# TeensyParser.net
KiCad netlist of a schematic drawn in EAGLE
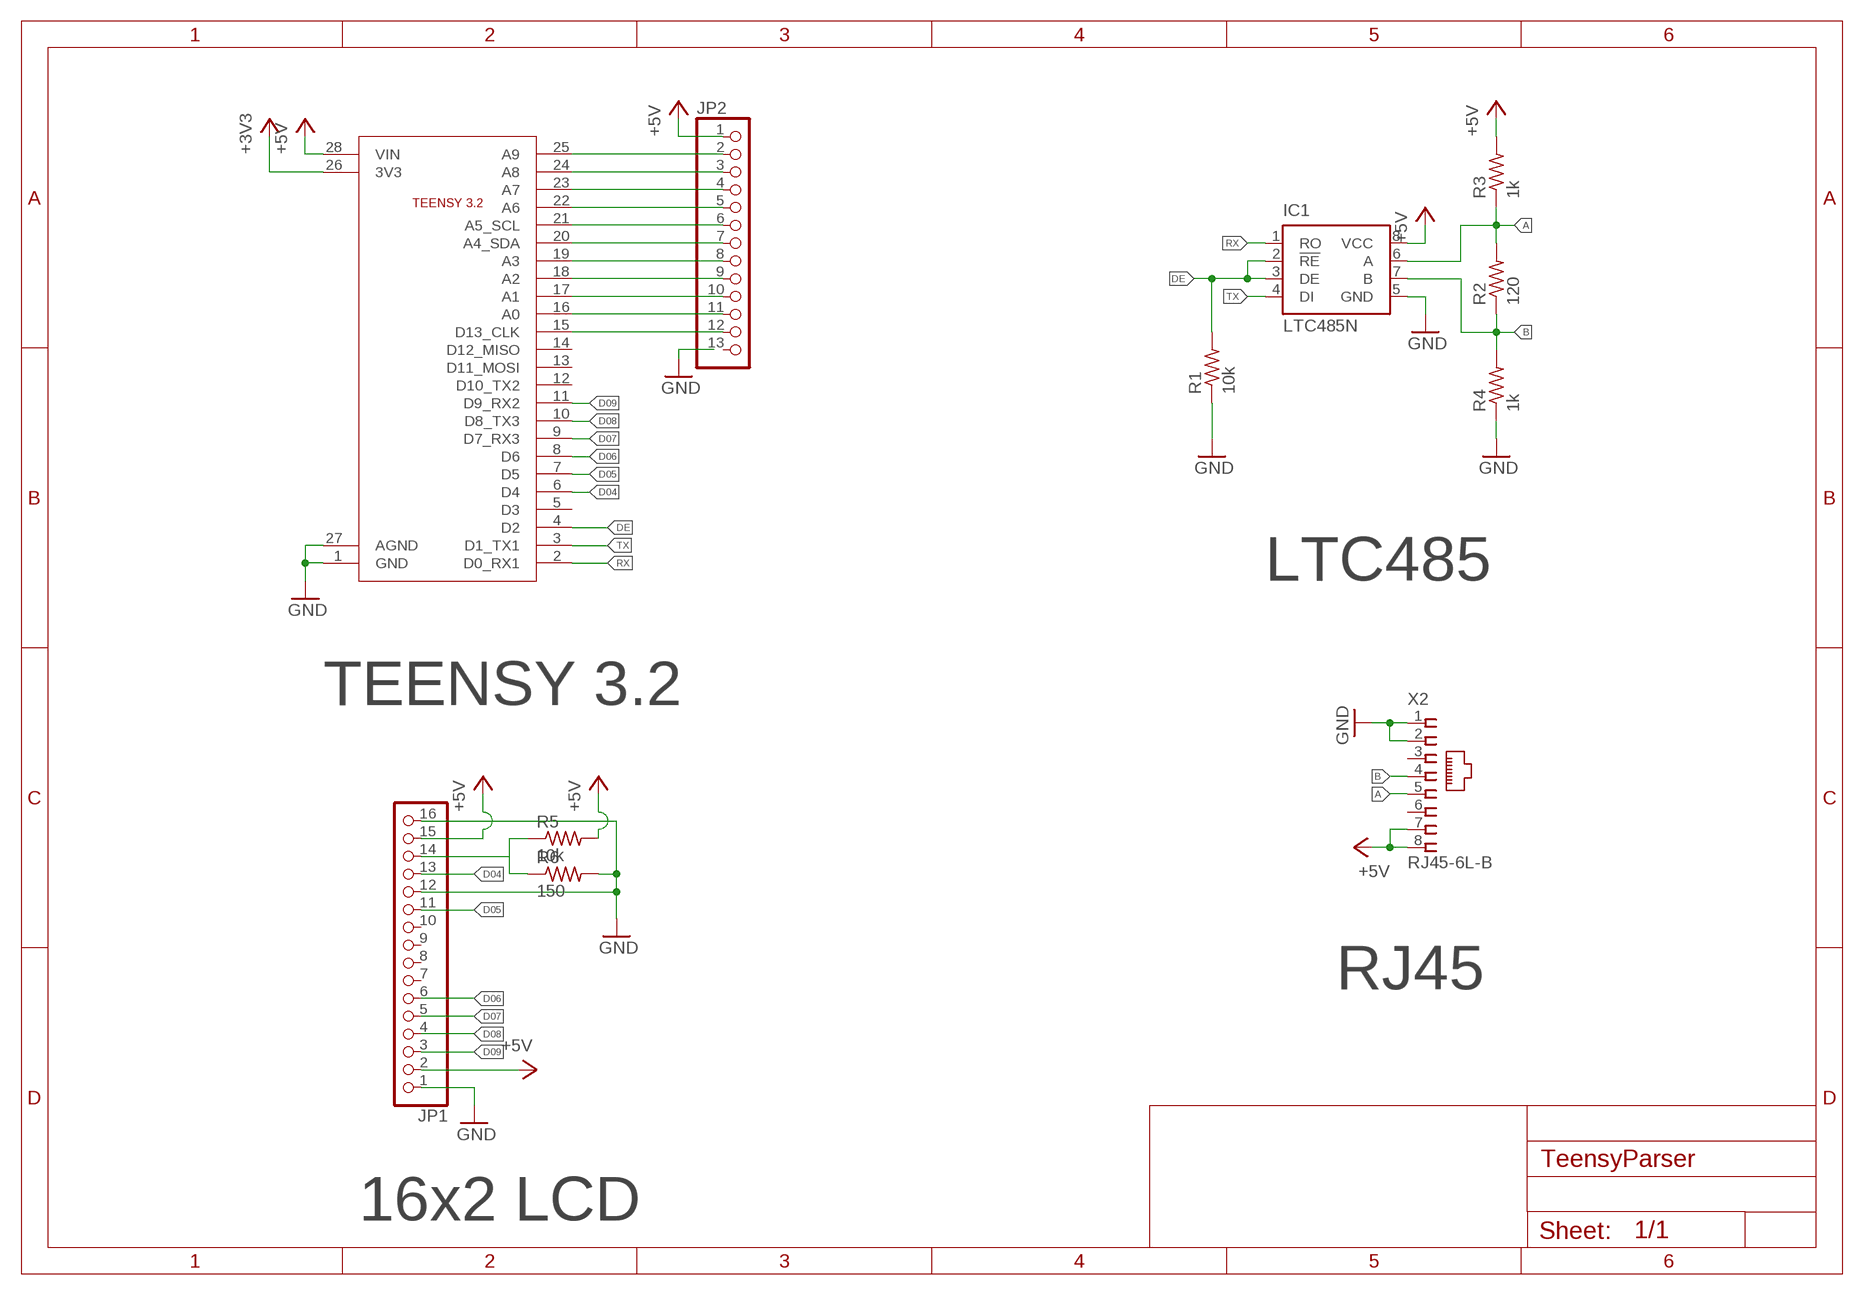
[diagram p0: schematic, sheet 1]

(export (version "E")
  (design (tool "Eeschema 10.0.6"))
  (components
    (comp (ref "IC1")
      (value "LTC485N")
      (footprint "eagle-import:DIL08")
      (libsource (lib "eagle-import") (part "LTC485N"))
    )
    (comp (ref "JP1")
      (value "PINHD-1X16")
      (footprint "eagle-import:1X16")
      (libsource (lib "eagle-import") (part "PINHD-1X16"))
    )
    (comp (ref "JP2")
      (value "PINHD-1X13")
      (footprint "eagle-import:1X13")
      (libsource (lib "eagle-import") (part "PINHD-1X13"))
    )
    (comp (ref "R1")
      (value "10k")
      (footprint "eagle-import:0204_7")
      (libsource (lib "eagle-import") (part "R-US_0204/7"))
    )
    (comp (ref "R2")
      (value "120")
      (footprint "eagle-import:0204_7")
      (libsource (lib "eagle-import") (part "R-US_0204/7"))
    )
    (comp (ref "R3")
      (value "1k")
      (footprint "eagle-import:0204_7")
      (libsource (lib "eagle-import") (part "R-US_0204/7"))
    )
    (comp (ref "R4")
      (value "1k")
      (footprint "eagle-import:0204_7")
      (libsource (lib "eagle-import") (part "R-US_0204/7"))
    )
    (comp (ref "R5")
      (value "10k")
      (footprint "eagle-import:0204_7")
      (libsource (lib "eagle-import") (part "R-US_0204/7"))
    )
    (comp (ref "R6")
      (value "150")
      (footprint "eagle-import:0204_7")
      (libsource (lib "eagle-import") (part "R-US_0204/7"))
    )
    (comp (ref "U$1")
      (value "TEENSY3.2")
      (footprint "eagle-import:TEENSY")
      (libsource (lib "eagle-import") (part "TEENSY3.2"))
    )
    (comp (ref "X2")
      (value "RJ45-6L-B")
      (footprint "eagle-import:RJ45-NO-SHIELD")
      (libsource (lib "eagle-import") (part "RJ45-6L-B"))
    )
  )
  (nets
    (net (code "1") (name "+3V3") (class "Default")
      (node (ref "U$1") (pin "26") (pinfunction "3V3_26") (pintype "bidirectional"))
    )
    (net (code "2") (name "+5V") (class "Default")
      (node (ref "IC1") (pin "8") (pinfunction "VCC_8") (pintype "input"))
      (node (ref "JP1") (pin "15") (pinfunction "15_15") (pintype "passive"))
      (node (ref "JP1") (pin "2") (pinfunction "2_2") (pintype "passive"))
      (node (ref "JP2") (pin "1") (pinfunction "1_1") (pintype "passive"))
      (node (ref "R3") (pin "2") (pinfunction "2_2") (pintype "passive"))
      (node (ref "R5") (pin "2") (pinfunction "2_2") (pintype "passive"))
      (node (ref "U$1") (pin "28") (pinfunction "VIN_28") (pintype "bidirectional"))
      (node (ref "X2") (pin "7") (pinfunction "7_7") (pintype "passive"))
      (node (ref "X2") (pin "8") (pinfunction "8_8") (pintype "passive"))
    )
    (net (code "3") (name "A") (class "Default")
      (node (ref "IC1") (pin "6") (pinfunction "A_6") (pintype "bidirectional"))
      (node (ref "R2") (pin "2") (pinfunction "2_2") (pintype "passive"))
      (node (ref "R3") (pin "1") (pinfunction "1_1") (pintype "passive"))
      (node (ref "X2") (pin "5") (pinfunction "5_5") (pintype "passive"))
    )
    (net (code "4") (name "B") (class "Default")
      (node (ref "IC1") (pin "7") (pinfunction "B_7") (pintype "bidirectional"))
      (node (ref "R2") (pin "1") (pinfunction "1_1") (pintype "passive"))
      (node (ref "R4") (pin "2") (pinfunction "2_2") (pintype "passive"))
      (node (ref "X2") (pin "4") (pinfunction "4_4") (pintype "passive"))
    )
    (net (code "5") (name "D04") (class "Default")
      (node (ref "JP1") (pin "13") (pinfunction "13_13") (pintype "passive"))
      (node (ref "U$1") (pin "6") (pinfunction "D4_6") (pintype "bidirectional"))
    )
    (net (code "6") (name "D05") (class "Default")
      (node (ref "JP1") (pin "11") (pinfunction "11_11") (pintype "passive"))
      (node (ref "U$1") (pin "7") (pinfunction "D5_7") (pintype "bidirectional"))
    )
    (net (code "7") (name "D06") (class "Default")
      (node (ref "JP1") (pin "6") (pinfunction "6_6") (pintype "passive"))
      (node (ref "U$1") (pin "8") (pinfunction "D6_8") (pintype "bidirectional"))
    )
    (net (code "8") (name "D07") (class "Default")
      (node (ref "JP1") (pin "5") (pinfunction "5_5") (pintype "passive"))
      (node (ref "U$1") (pin "9") (pinfunction "D7_RX3_9") (pintype "bidirectional"))
    )
    (net (code "9") (name "D08") (class "Default")
      (node (ref "JP1") (pin "4") (pinfunction "4_4") (pintype "passive"))
      (node (ref "U$1") (pin "10") (pinfunction "D8_TX3_10") (pintype "bidirectional"))
    )
    (net (code "10") (name "D09") (class "Default")
      (node (ref "JP1") (pin "3") (pinfunction "3_3") (pintype "passive"))
      (node (ref "U$1") (pin "11") (pinfunction "D9_RX2_11") (pintype "bidirectional"))
    )
    (net (code "11") (name "DE") (class "Default")
      (node (ref "IC1") (pin "2") (pinfunction "~{RE}_2") (pintype "input"))
      (node (ref "IC1") (pin "3") (pinfunction "DE_3") (pintype "input"))
      (node (ref "R1") (pin "2") (pinfunction "2_2") (pintype "passive"))
      (node (ref "U$1") (pin "4") (pinfunction "D2_4") (pintype "bidirectional"))
    )
    (net (code "12") (name "GND") (class "Default")
      (node (ref "IC1") (pin "5") (pinfunction "GND_5") (pintype "input"))
      (node (ref "JP1") (pin "1") (pinfunction "1_1") (pintype "passive"))
      (node (ref "JP1") (pin "12") (pinfunction "12_12") (pintype "passive"))
      (node (ref "JP1") (pin "16") (pinfunction "16_16") (pintype "passive"))
      (node (ref "R1") (pin "1") (pinfunction "1_1") (pintype "passive"))
      (node (ref "R4") (pin "1") (pinfunction "1_1") (pintype "passive"))
      (node (ref "R6") (pin "2") (pinfunction "2_2") (pintype "passive"))
      (node (ref "U$1") (pin "1") (pinfunction "GND_1") (pintype "bidirectional"))
      (node (ref "U$1") (pin "27") (pinfunction "AGND_27") (pintype "bidirectional"))
      (node (ref "X2") (pin "1") (pinfunction "1_1") (pintype "passive"))
      (node (ref "X2") (pin "2") (pinfunction "2_2") (pintype "passive"))
    )
    (net (code "13") (name "Net-(JP1-Pad14)") (class "Default")
      (node (ref "JP1") (pin "14") (pinfunction "14_14") (pintype "passive"))
      (node (ref "R5") (pin "1") (pinfunction "1_1") (pintype "passive"))
      (node (ref "R6") (pin "1") (pinfunction "1_1") (pintype "passive"))
    )
    (net (code "14") (name "Net-(U$1-A0)") (class "Default")
      (node (ref "JP2") (pin "11") (pinfunction "11_11") (pintype "passive"))
      (node (ref "U$1") (pin "16") (pinfunction "A0_16") (pintype "bidirectional"))
    )
    (net (code "15") (name "Net-(U$1-A1)") (class "Default")
      (node (ref "JP2") (pin "10") (pinfunction "10_10") (pintype "passive"))
      (node (ref "U$1") (pin "17") (pinfunction "A1_17") (pintype "bidirectional"))
    )
    (net (code "16") (name "Net-(U$1-A2)") (class "Default")
      (node (ref "JP2") (pin "9") (pinfunction "9_9") (pintype "passive"))
      (node (ref "U$1") (pin "18") (pinfunction "A2_18") (pintype "bidirectional"))
    )
    (net (code "17") (name "Net-(U$1-A3)") (class "Default")
      (node (ref "JP2") (pin "8") (pinfunction "8_8") (pintype "passive"))
      (node (ref "U$1") (pin "19") (pinfunction "A3_19") (pintype "bidirectional"))
    )
    (net (code "18") (name "Net-(U$1-A4_SDA)") (class "Default")
      (node (ref "JP2") (pin "7") (pinfunction "7_7") (pintype "passive"))
      (node (ref "U$1") (pin "20") (pinfunction "A4_SDA_20") (pintype "bidirectional"))
    )
    (net (code "19") (name "Net-(U$1-A5_SCL)") (class "Default")
      (node (ref "JP2") (pin "6") (pinfunction "6_6") (pintype "passive"))
      (node (ref "U$1") (pin "21") (pinfunction "A5_SCL_21") (pintype "bidirectional"))
    )
    (net (code "20") (name "Net-(U$1-A6)") (class "Default")
      (node (ref "JP2") (pin "5") (pinfunction "5_5") (pintype "passive"))
      (node (ref "U$1") (pin "22") (pinfunction "A6_22") (pintype "bidirectional"))
    )
    (net (code "21") (name "Net-(U$1-A7)") (class "Default")
      (node (ref "JP2") (pin "4") (pinfunction "4_4") (pintype "passive"))
      (node (ref "U$1") (pin "23") (pinfunction "A7_23") (pintype "bidirectional"))
    )
    (net (code "22") (name "Net-(U$1-A8)") (class "Default")
      (node (ref "JP2") (pin "3") (pinfunction "3_3") (pintype "passive"))
      (node (ref "U$1") (pin "24") (pinfunction "A8_24") (pintype "bidirectional"))
    )
    (net (code "23") (name "Net-(U$1-A9)") (class "Default")
      (node (ref "JP2") (pin "2") (pinfunction "2_2") (pintype "passive"))
      (node (ref "U$1") (pin "25") (pinfunction "A9_25") (pintype "bidirectional"))
    )
    (net (code "24") (name "Net-(U$1-D13_CLK)") (class "Default")
      (node (ref "JP2") (pin "12") (pinfunction "12_12") (pintype "passive"))
      (node (ref "U$1") (pin "15") (pinfunction "D13_CLK_15") (pintype "bidirectional"))
    )
    (net (code "25") (name "RX") (class "Default")
      (node (ref "IC1") (pin "1") (pinfunction "RO_1") (pintype "output"))
      (node (ref "U$1") (pin "2") (pinfunction "D0_RX1_2") (pintype "bidirectional"))
    )
    (net (code "26") (name "TX") (class "Default")
      (node (ref "IC1") (pin "4") (pinfunction "DI_4") (pintype "input"))
      (node (ref "U$1") (pin "3") (pinfunction "D1_TX1_3") (pintype "bidirectional"))
    )
    (net (code "27") (name "unconnected-(JP1-Pad7)") (class "Default")
      (node (ref "JP1") (pin "7") (pinfunction "7_7") (pintype "passive"))
    )
    (net (code "28") (name "unconnected-(JP1-Pad8)") (class "Default")
      (node (ref "JP1") (pin "8") (pinfunction "8_8") (pintype "passive"))
    )
    (net (code "29") (name "unconnected-(JP1-Pad9)") (class "Default")
      (node (ref "JP1") (pin "9") (pinfunction "9_9") (pintype "passive"))
    )
    (net (code "30") (name "unconnected-(JP1-Pad10)") (class "Default")
      (node (ref "JP1") (pin "10") (pinfunction "10_10") (pintype "passive"))
    )
    (net (code "31") (name "unconnected-(JP2-Pad13)") (class "Default")
      (node (ref "JP2") (pin "13") (pinfunction "13_13") (pintype "passive"))
    )
    (net (code "32") (name "unconnected-(U$1-D3-Pad5)") (class "Default")
      (node (ref "U$1") (pin "5") (pinfunction "D3_5") (pintype "bidirectional"))
    )
    (net (code "33") (name "unconnected-(U$1-D10_TX2-Pad12)") (class "Default")
      (node (ref "U$1") (pin "12") (pinfunction "D10_TX2_12") (pintype "bidirectional"))
    )
    (net (code "34") (name "unconnected-(U$1-D11_MOSI-Pad13)") (class "Default")
      (node (ref "U$1") (pin "13") (pinfunction "D11_MOSI_13") (pintype "bidirectional"))
    )
    (net (code "35") (name "unconnected-(U$1-D12_MISO-Pad14)") (class "Default")
      (node (ref "U$1") (pin "14") (pinfunction "D12_MISO_14") (pintype "bidirectional"))
    )
    (net (code "36") (name "unconnected-(X2-Pad3)") (class "Default")
      (node (ref "X2") (pin "3") (pinfunction "3_3") (pintype "passive"))
    )
    (net (code "37") (name "unconnected-(X2-Pad6)") (class "Default")
      (node (ref "X2") (pin "6") (pinfunction "6_6") (pintype "passive"))
    )
  )
)
